# DCDC_2.net
KiCad netlist of a schematic drawn in Altium Designer
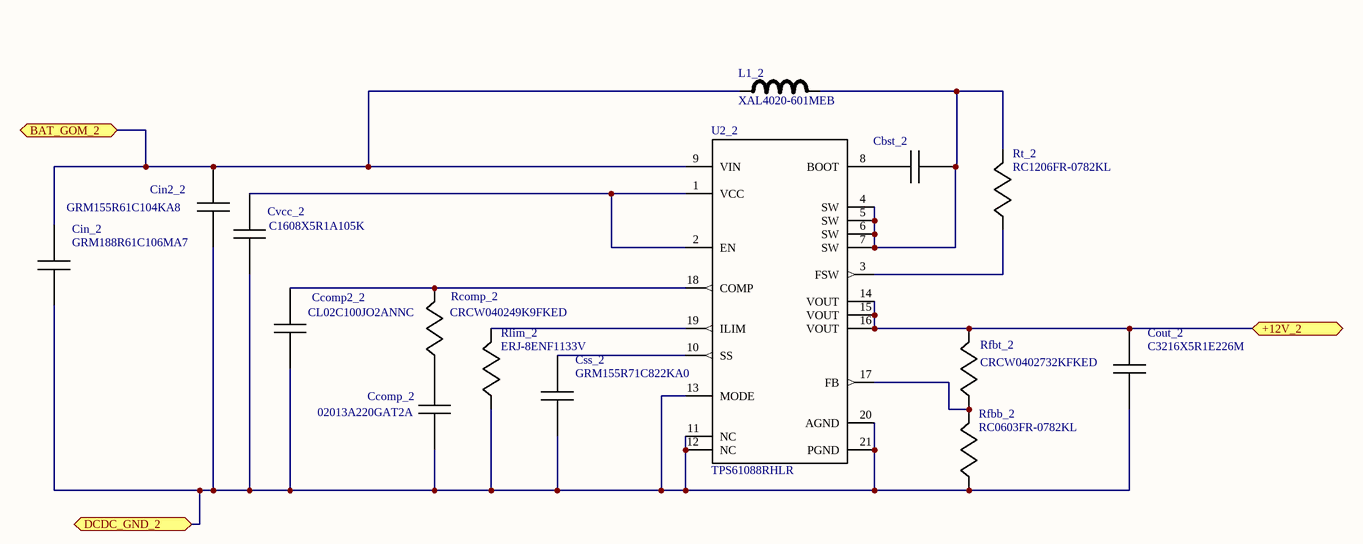
[diagram p0: DCDC_2.SchDoc]

(export (version "E")
  (design (tool "Eeschema 10.0.6"))
  (components
    (comp (ref "Cbst_2")
      (value "C1005X5R1A104K")
      (footprint "1005")
      (description "Imported")
      (libsource (lib "2015-10-09_12-54-35") (part "C1005X5R1A104K"))
    )
    (comp (ref "Ccomp2_2")
      (value "CL02C100JO2ANNC")
      (footprint "01005")
      (description "Imported")
      (libsource (lib "2015-10-09_12-54-35") (part "CL02C100JO2ANNC"))
    )
    (comp (ref "Ccomp_2")
      (value "02013A220GAT2A")
      (footprint "0201")
      (description "Imported")
      (libsource (lib "2015-10-09_12-54-35") (part "02013A220GAT2A"))
    )
    (comp (ref "Cin2_2")
      (value "GRM155R61C104KA8")
      (footprint "0402")
      (description "Imported")
      (fields (field (name "MANUFACTURER_PART_NUMBER") "GRM155R61C104KA88D"))
      (libsource (lib "2015-10-09_12-54-35") (part "GRM155R61C104KA8"))
    )
    (comp (ref "Cin_2")
      (value "GRM188R61C106MA7")
      (footprint "0603")
      (description "Imported")
      (fields (field (name "MANUFACTURER_PART_NUMBER") "GRM188R61C106MA73D"))
      (libsource (lib "2015-10-09_12-54-35") (part "GRM188R61C106MA7"))
    )
    (comp (ref "Cout_2")
      (value "C3216X5R1E226M")
      (footprint "1206")
      (description "Imported")
      (libsource (lib "2015-10-09_12-54-35") (part "C3216X5R1E226M"))
    )
    (comp (ref "Css_2")
      (value "GRM155R71C822KA0")
      (footprint "0402")
      (description "Imported")
      (fields (field (name "MANUFACTURER_PART_NUMBER") "GRM155R71C822KA01D"))
      (libsource (lib "2015-10-09_12-54-35") (part "GRM155R71C822KA0"))
    )
    (comp (ref "Cvcc_2")
      (value "C1608X5R1A105K")
      (footprint "1608")
      (description "Imported")
      (libsource (lib "2015-10-09_12-54-35") (part "C1608X5R1A105K"))
    )
    (comp (ref "L1_2")
      (value "XAL4020-601MEB")
      (footprint "XAL4020")
      (description "Imported")
      (libsource (lib "2015-10-09_12-54-35") (part "XAL4020-601MEB"))
    )
    (comp (ref "Rcomp_2")
      (value "CRCW040249K9FKED")
      (footprint "0402")
      (description "Imported")
      (libsource (lib "2015-10-09_12-54-35") (part "CRCW040249K9FKED"))
    )
    (comp (ref "Rfbb_2")
      (value "RC0603FR-0782KL")
      (footprint "0603")
      (description "Imported")
      (libsource (lib "2015-10-09_12-54-35") (part "RC0603FR-0782KL"))
    )
    (comp (ref "Rfbt_2")
      (value "CRCW0402732KFKED")
      (footprint "0402")
      (description "Imported")
      (libsource (lib "2015-10-09_12-54-35") (part "CRCW0402732KFKED"))
    )
    (comp (ref "Rlim_2")
      (value "ERJ-8ENF1133V")
      (footprint "1206")
      (description "Imported")
      (libsource (lib "2015-10-09_12-54-35") (part "ERJ-8ENF1133V"))
    )
    (comp (ref "Rt_2")
      (value "RC1206FR-0782KL")
      (footprint "1206")
      (description "Imported")
      (libsource (lib "2015-10-09_12-54-35") (part "RC1206FR-0782KL"))
    )
    (comp (ref "U2_2")
      (value "TPS61088RHLR")
      (footprint "RHL0020A")
      (description "Imported")
      (fields
        (field (name "ALTERNATE PARTNUMBER") "TPS61088RHLT")
        (field (name "MANUFACTURER") "Texas Instruments")
      )
      (libsource (lib "2015-10-09_12-53-27") (part "TPS61088RHLR"))
    )
  )
  (nets
    (net (code "1") (name "/+12V_2") (class "Default")
      (node (ref "Cout_2") (pin "1") (pinfunction "1_1") (pintype "passive"))
      (node (ref "Rfbt_2") (pin "1") (pinfunction "1_1") (pintype "passive"))
      (node (ref "U2_2") (pin "14") (pinfunction "VOUT_14") (pintype "passive"))
      (node (ref "U2_2") (pin "15") (pinfunction "VOUT_15") (pintype "passive"))
      (node (ref "U2_2") (pin "16") (pinfunction "VOUT_16") (pintype "passive"))
    )
    (net (code "2") (name "/BAT_GOM_2") (class "Default")
      (node (ref "Cin2_2") (pin "1") (pinfunction "1_1") (pintype "passive"))
      (node (ref "Cin_2") (pin "1") (pinfunction "1_1") (pintype "passive"))
      (node (ref "L1_2") (pin "1") (pinfunction "1_1") (pintype "passive"))
      (node (ref "U2_2") (pin "9") (pinfunction "VIN_9") (pintype "passive"))
    )
    (net (code "3") (name "/DCDC_GND_2") (class "Default")
      (node (ref "Ccomp2_2") (pin "1") (pinfunction "1_1") (pintype "passive"))
      (node (ref "Ccomp_2") (pin "2") (pinfunction "2_2") (pintype "passive"))
      (node (ref "Cin2_2") (pin "2") (pinfunction "2_2") (pintype "passive"))
      (node (ref "Cin_2") (pin "2") (pinfunction "2_2") (pintype "passive"))
      (node (ref "Cout_2") (pin "2") (pinfunction "2_2") (pintype "passive"))
      (node (ref "Css_2") (pin "1") (pinfunction "1_1") (pintype "passive"))
      (node (ref "Cvcc_2") (pin "1") (pinfunction "1_1") (pintype "passive"))
      (node (ref "Rfbb_2") (pin "2") (pinfunction "2_2") (pintype "passive"))
      (node (ref "Rlim_2") (pin "2") (pinfunction "2_2") (pintype "passive"))
      (node (ref "U2_2") (pin "11") (pinfunction "NC_11") (pintype "passive"))
      (node (ref "U2_2") (pin "12") (pinfunction "NC_12") (pintype "passive"))
      (node (ref "U2_2") (pin "13") (pinfunction "MODE_13") (pintype "passive"))
      (node (ref "U2_2") (pin "20") (pinfunction "AGND_20") (pintype "passive"))
      (node (ref "U2_2") (pin "21") (pinfunction "PGND_21") (pintype "passive"))
    )
    (net (code "4") (name "Net-(Cbst_2-Pad1)") (class "Default")
      (node (ref "Cbst_2") (pin "1") (pinfunction "1_1") (pintype "passive"))
      (node (ref "L1_2") (pin "2") (pinfunction "2_2") (pintype "passive"))
      (node (ref "Rt_2") (pin "1") (pinfunction "1_1") (pintype "passive"))
      (node (ref "U2_2") (pin "4") (pinfunction "SW_4") (pintype "power_in"))
      (node (ref "U2_2") (pin "5") (pinfunction "SW_5") (pintype "power_in"))
      (node (ref "U2_2") (pin "6") (pinfunction "SW_6") (pintype "power_in"))
      (node (ref "U2_2") (pin "7") (pinfunction "SW_7") (pintype "power_in"))
    )
    (net (code "5") (name "Net-(Ccomp_2-Pad1)") (class "Default")
      (node (ref "Ccomp_2") (pin "1") (pinfunction "1_1") (pintype "passive"))
      (node (ref "Rcomp_2") (pin "2") (pinfunction "2_2") (pintype "passive"))
    )
    (net (code "6") (name "Net-(U2_2-BOOT)") (class "Default")
      (node (ref "Cbst_2") (pin "2") (pinfunction "2_2") (pintype "passive"))
      (node (ref "U2_2") (pin "8") (pinfunction "BOOT_8") (pintype "power_in"))
    )
    (net (code "7") (name "Net-(U2_2-COMP)") (class "Default")
      (node (ref "Ccomp2_2") (pin "2") (pinfunction "2_2") (pintype "passive"))
      (node (ref "Rcomp_2") (pin "1") (pinfunction "1_1") (pintype "passive"))
      (node (ref "U2_2") (pin "18") (pinfunction "COMP_18") (pintype "output"))
    )
    (net (code "8") (name "Net-(U2_2-EN)") (class "Default")
      (node (ref "Cvcc_2") (pin "2") (pinfunction "2_2") (pintype "passive"))
      (node (ref "U2_2") (pin "1") (pinfunction "VCC_1") (pintype "passive"))
      (node (ref "U2_2") (pin "2") (pinfunction "EN_2") (pintype "passive"))
    )
    (net (code "9") (name "Net-(U2_2-FB)") (class "Default")
      (node (ref "Rfbb_2") (pin "1") (pinfunction "1_1") (pintype "passive"))
      (node (ref "Rfbt_2") (pin "2") (pinfunction "2_2") (pintype "passive"))
      (node (ref "U2_2") (pin "17") (pinfunction "FB_17") (pintype "output"))
    )
    (net (code "10") (name "Net-(U2_2-FSW)") (class "Default")
      (node (ref "Rt_2") (pin "2") (pinfunction "2_2") (pintype "passive"))
      (node (ref "U2_2") (pin "3") (pinfunction "FSW_3") (pintype "output"))
    )
    (net (code "11") (name "Net-(U2_2-ILIM)") (class "Default")
      (node (ref "Rlim_2") (pin "1") (pinfunction "1_1") (pintype "passive"))
      (node (ref "U2_2") (pin "19") (pinfunction "ILIM_19") (pintype "output"))
    )
    (net (code "12") (name "Net-(U2_2-SS)") (class "Default")
      (node (ref "Css_2") (pin "2") (pinfunction "2_2") (pintype "passive"))
      (node (ref "U2_2") (pin "10") (pinfunction "SS_10") (pintype "output"))
    )
  )
)
